# CircularLED.net
KiCad netlist of a schematic drawn in Altium Designer
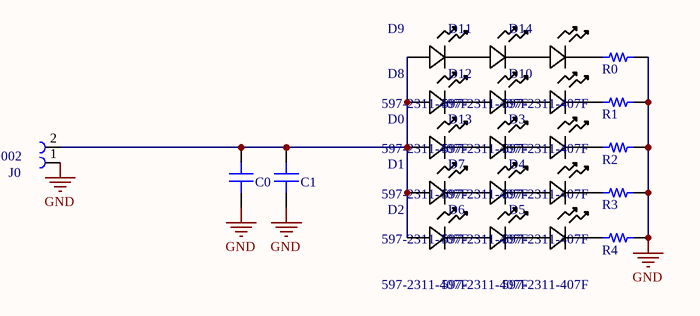
[diagram p0: CircularLED.SchDoc]

(export (version "E")
  (design (tool "Eeschema 10.0.6"))
  (components
    (comp (ref "C0")
      (value "4.7uF")
      (footprint "CAP 0402/1005")
      (description "CAP CER 4.7UF 10V X5R 0402")
      (fields
        (field (name "PART NUMBER") "C1005X5R1A475K050BC")
        (field (name "MANUFACTURER") "TDK Corporation")
      )
      (libsource (lib "Celestial Library Database") (part "Capacitor"))
    )
    (comp (ref "C1")
      (value "0.1uF")
      (footprint "CAP 0402/1005")
      (description "CAP CER 0.1UF 16V X7R 0402")
      (fields
        (field (name "PART NUMBER") "C1005X7R1C104K050BC")
        (field (name "MANUFACTURER") "TDK Corporation")
      )
      (libsource (lib "Celestial Library Database") (part "Capacitor"))
    )
    (comp (ref "D0")
      (value "597-2311-407F")
      (footprint "LED_597-2311-407F")
      (description "597 Series Green 2 mm 130Â° Water Clear 5.2 mcd 2.1 V LED Surface Mount")
      (fields (field (name "MF") "Dialight"))
      (libsource (lib "597-2311-407F") (part "597-2311-407F"))
    )
    (comp (ref "D1")
      (value "597-2311-407F")
      (footprint "LED_597-2311-407F")
      (description "597 Series Green 2 mm 130Â° Water Clear 5.2 mcd 2.1 V LED Surface Mount")
      (fields (field (name "MF") "Dialight"))
      (libsource (lib "597-2311-407F") (part "597-2311-407F"))
    )
    (comp (ref "D2")
      (value "597-2311-407F")
      (footprint "LED_597-2311-407F")
      (description "597 Series Green 2 mm 130Â° Water Clear 5.2 mcd 2.1 V LED Surface Mount")
      (fields (field (name "MF") "Dialight"))
      (libsource (lib "597-2311-407F") (part "597-2311-407F"))
    )
    (comp (ref "D3")
      (value "597-2311-407F")
      (footprint "LED_597-2311-407F")
      (description "597 Series Green 2 mm 130Â° Water Clear 5.2 mcd 2.1 V LED Surface Mount")
      (fields (field (name "MF") "Dialight"))
      (libsource (lib "597-2311-407F") (part "597-2311-407F"))
    )
    (comp (ref "D4")
      (value "597-2311-407F")
      (footprint "LED_597-2311-407F")
      (description "597 Series Green 2 mm 130Â° Water Clear 5.2 mcd 2.1 V LED Surface Mount")
      (fields (field (name "MF") "Dialight"))
      (libsource (lib "597-2311-407F") (part "597-2311-407F"))
    )
    (comp (ref "D5")
      (value "597-2311-407F")
      (footprint "LED_597-2311-407F")
      (description "597 Series Green 2 mm 130Â° Water Clear 5.2 mcd 2.1 V LED Surface Mount")
      (fields (field (name "MF") "Dialight"))
      (libsource (lib "597-2311-407F") (part "597-2311-407F"))
    )
    (comp (ref "D6")
      (value "597-2311-407F")
      (footprint "LED_597-2311-407F")
      (description "597 Series Green 2 mm 130Â° Water Clear 5.2 mcd 2.1 V LED Surface Mount")
      (fields (field (name "MF") "Dialight"))
      (libsource (lib "597-2311-407F") (part "597-2311-407F"))
    )
    (comp (ref "D7")
      (value "597-2311-407F")
      (footprint "LED_597-2311-407F")
      (description "597 Series Green 2 mm 130Â° Water Clear 5.2 mcd 2.1 V LED Surface Mount")
      (fields (field (name "MF") "Dialight"))
      (libsource (lib "597-2311-407F") (part "597-2311-407F"))
    )
    (comp (ref "D8")
      (value "597-2311-407F")
      (footprint "LED_597-2311-407F")
      (description "597 Series Green 2 mm 130Â° Water Clear 5.2 mcd 2.1 V LED Surface Mount")
      (fields (field (name "MF") "Dialight"))
      (libsource (lib "597-2311-407F") (part "597-2311-407F"))
    )
    (comp (ref "D9")
      (value "597-2311-407F")
      (footprint "LED_597-2311-407F")
      (description "597 Series Green 2 mm 130Â° Water Clear 5.2 mcd 2.1 V LED Surface Mount")
      (fields (field (name "MF") "Dialight"))
      (libsource (lib "597-2311-407F") (part "597-2311-407F"))
    )
    (comp (ref "D10")
      (value "597-2311-407F")
      (footprint "LED_597-2311-407F")
      (description "597 Series Green 2 mm 130Â° Water Clear 5.2 mcd 2.1 V LED Surface Mount")
      (fields (field (name "MF") "Dialight"))
      (libsource (lib "597-2311-407F") (part "597-2311-407F"))
    )
    (comp (ref "D11")
      (value "597-2311-407F")
      (footprint "LED_597-2311-407F")
      (description "597 Series Green 2 mm 130Â° Water Clear 5.2 mcd 2.1 V LED Surface Mount")
      (fields (field (name "MF") "Dialight"))
      (libsource (lib "597-2311-407F") (part "597-2311-407F"))
    )
    (comp (ref "D12")
      (value "597-2311-407F")
      (footprint "LED_597-2311-407F")
      (description "597 Series Green 2 mm 130Â° Water Clear 5.2 mcd 2.1 V LED Surface Mount")
      (fields (field (name "MF") "Dialight"))
      (libsource (lib "597-2311-407F") (part "597-2311-407F"))
    )
    (comp (ref "D13")
      (value "597-2311-407F")
      (footprint "LED_597-2311-407F")
      (description "597 Series Green 2 mm 130Â° Water Clear 5.2 mcd 2.1 V LED Surface Mount")
      (fields (field (name "MF") "Dialight"))
      (libsource (lib "597-2311-407F") (part "597-2311-407F"))
    )
    (comp (ref "D14")
      (value "597-2311-407F")
      (footprint "LED_597-2311-407F")
      (description "597 Series Green 2 mm 130Â° Water Clear 5.2 mcd 2.1 V LED Surface Mount")
      (fields (field (name "MF") "Dialight"))
      (libsource (lib "597-2311-407F") (part "597-2311-407F"))
    )
    (comp (ref "J0")
      (value "691102710002")
      (footprint "691102710002")
      (description "Screw terminal 0.33 mmÂ² Number of pins 2 Wuerth Elektronik Blue 1 pc_s_")
      (fields (field (name "MF") "Wurth Electronics"))
      (libsource (lib "691102710002") (part "691102710002"))
    )
    (comp (ref "R0")
      (value "200")
      (footprint "RES 0402/1005")
      (description "RES SMD 200 OHM 1% 1/10W 0402")
      (fields
        (field (name "PART NUMBER") "ERJ-2RKF2000X")
        (field (name "MANUFACTURER") "Panasonic Electronic Components")
      )
      (libsource (lib "Celestial Library Database") (part "Resistor"))
    )
    (comp (ref "R1")
      (value "200")
      (footprint "RES 0402/1005")
      (description "RES SMD 200 OHM 1% 1/10W 0402")
      (fields
        (field (name "PART NUMBER") "ERJ-2RKF2000X")
        (field (name "MANUFACTURER") "Panasonic Electronic Components")
      )
      (libsource (lib "Celestial Library Database") (part "Resistor"))
    )
    (comp (ref "R2")
      (value "200")
      (footprint "RES 0402/1005")
      (description "RES SMD 200 OHM 1% 1/10W 0402")
      (fields
        (field (name "PART NUMBER") "ERJ-2RKF2000X")
        (field (name "MANUFACTURER") "Panasonic Electronic Components")
      )
      (libsource (lib "Celestial Library Database") (part "Resistor"))
    )
    (comp (ref "R3")
      (value "200")
      (footprint "RES 0402/1005")
      (description "RES SMD 200 OHM 1% 1/10W 0402")
      (fields
        (field (name "PART NUMBER") "ERJ-2RKF2000X")
        (field (name "MANUFACTURER") "Panasonic Electronic Components")
      )
      (libsource (lib "Celestial Library Database") (part "Resistor"))
    )
    (comp (ref "R4")
      (value "200")
      (footprint "RES 0402/1005")
      (description "RES SMD 200 OHM 1% 1/10W 0402")
      (fields
        (field (name "PART NUMBER") "ERJ-2RKF2000X")
        (field (name "MANUFACTURER") "Panasonic Electronic Components")
      )
      (libsource (lib "Celestial Library Database") (part "Resistor"))
    )
  )
  (nets
    (net (code "1") (name "GND") (class "Default")
      (node (ref "C0") (pin "1") (pinfunction "1_1") (pintype "passive"))
      (node (ref "C1") (pin "1") (pinfunction "1_1") (pintype "passive"))
      (node (ref "J0") (pin "1") (pinfunction "1_1") (pintype "passive"))
      (node (ref "R0") (pin "2") (pinfunction "2_2") (pintype "passive"))
      (node (ref "R1") (pin "2") (pinfunction "2_2") (pintype "passive"))
      (node (ref "R2") (pin "2") (pinfunction "2_2") (pintype "passive"))
      (node (ref "R3") (pin "2") (pinfunction "2_2") (pintype "passive"))
      (node (ref "R4") (pin "2") (pinfunction "2_2") (pintype "passive"))
    )
    (net (code "2") (name "Net-(C0-Pad2)") (class "Default")
      (node (ref "C0") (pin "2") (pinfunction "2_2") (pintype "passive"))
      (node (ref "C1") (pin "2") (pinfunction "2_2") (pintype "passive"))
      (node (ref "D0") (pin "2") (pinfunction "2_2") (pintype "passive"))
      (node (ref "D1") (pin "2") (pinfunction "2_2") (pintype "passive"))
      (node (ref "D2") (pin "2") (pinfunction "2_2") (pintype "passive"))
      (node (ref "D8") (pin "2") (pinfunction "2_2") (pintype "passive"))
      (node (ref "D9") (pin "2") (pinfunction "2_2") (pintype "passive"))
      (node (ref "J0") (pin "2") (pinfunction "2_2") (pintype "passive"))
    )
    (net (code "3") (name "Net-(D0-Pad1)") (class "Default")
      (node (ref "D0") (pin "1") (pinfunction "1_1") (pintype "passive"))
      (node (ref "D13") (pin "2") (pinfunction "2_2") (pintype "passive"))
    )
    (net (code "4") (name "Net-(D1-Pad1)") (class "Default")
      (node (ref "D1") (pin "1") (pinfunction "1_1") (pintype "passive"))
      (node (ref "D7") (pin "2") (pinfunction "2_2") (pintype "passive"))
    )
    (net (code "5") (name "Net-(D2-Pad1)") (class "Default")
      (node (ref "D2") (pin "1") (pinfunction "1_1") (pintype "passive"))
      (node (ref "D6") (pin "2") (pinfunction "2_2") (pintype "passive"))
    )
    (net (code "6") (name "Net-(D3-Pad1)") (class "Default")
      (node (ref "D3") (pin "1") (pinfunction "1_1") (pintype "passive"))
      (node (ref "R2") (pin "1") (pinfunction "1_1") (pintype "passive"))
    )
    (net (code "7") (name "Net-(D4-Pad1)") (class "Default")
      (node (ref "D4") (pin "1") (pinfunction "1_1") (pintype "passive"))
      (node (ref "R3") (pin "1") (pinfunction "1_1") (pintype "passive"))
    )
    (net (code "8") (name "Net-(D4-Pad2)") (class "Default")
      (node (ref "D4") (pin "2") (pinfunction "2_2") (pintype "passive"))
      (node (ref "D7") (pin "1") (pinfunction "1_1") (pintype "passive"))
    )
    (net (code "9") (name "Net-(D5-Pad1)") (class "Default")
      (node (ref "D5") (pin "1") (pinfunction "1_1") (pintype "passive"))
      (node (ref "R4") (pin "1") (pinfunction "1_1") (pintype "passive"))
    )
    (net (code "10") (name "Net-(D5-Pad2)") (class "Default")
      (node (ref "D5") (pin "2") (pinfunction "2_2") (pintype "passive"))
      (node (ref "D6") (pin "1") (pinfunction "1_1") (pintype "passive"))
    )
    (net (code "11") (name "Net-(D10-Pad1)") (class "Default")
      (node (ref "D10") (pin "1") (pinfunction "1_1") (pintype "passive"))
      (node (ref "R1") (pin "1") (pinfunction "1_1") (pintype "passive"))
    )
    (net (code "12") (name "Net-(D10-Pad2)") (class "Default")
      (node (ref "D10") (pin "2") (pinfunction "2_2") (pintype "passive"))
      (node (ref "D12") (pin "1") (pinfunction "1_1") (pintype "passive"))
    )
    (net (code "13") (name "Net-(D11-Pad1)") (class "Default")
      (node (ref "D11") (pin "1") (pinfunction "1_1") (pintype "passive"))
      (node (ref "D14") (pin "2") (pinfunction "2_2") (pintype "passive"))
    )
    (net (code "14") (name "Net-(D11-Pad2)") (class "Default")
      (node (ref "D11") (pin "2") (pinfunction "2_2") (pintype "passive"))
      (node (ref "D9") (pin "1") (pinfunction "1_1") (pintype "passive"))
    )
    (net (code "15") (name "Net-(D12-Pad2)") (class "Default")
      (node (ref "D12") (pin "2") (pinfunction "2_2") (pintype "passive"))
      (node (ref "D8") (pin "1") (pinfunction "1_1") (pintype "passive"))
    )
    (net (code "16") (name "Net-(D13-Pad1)") (class "Default")
      (node (ref "D13") (pin "1") (pinfunction "1_1") (pintype "passive"))
      (node (ref "D3") (pin "2") (pinfunction "2_2") (pintype "passive"))
    )
    (net (code "17") (name "Net-(D14-Pad1)") (class "Default")
      (node (ref "D14") (pin "1") (pinfunction "1_1") (pintype "passive"))
      (node (ref "R0") (pin "1") (pinfunction "1_1") (pintype "passive"))
    )
  )
)
